# mainboard_interface_v1_1.net
KiCad netlist of a schematic drawn in Altium Designer
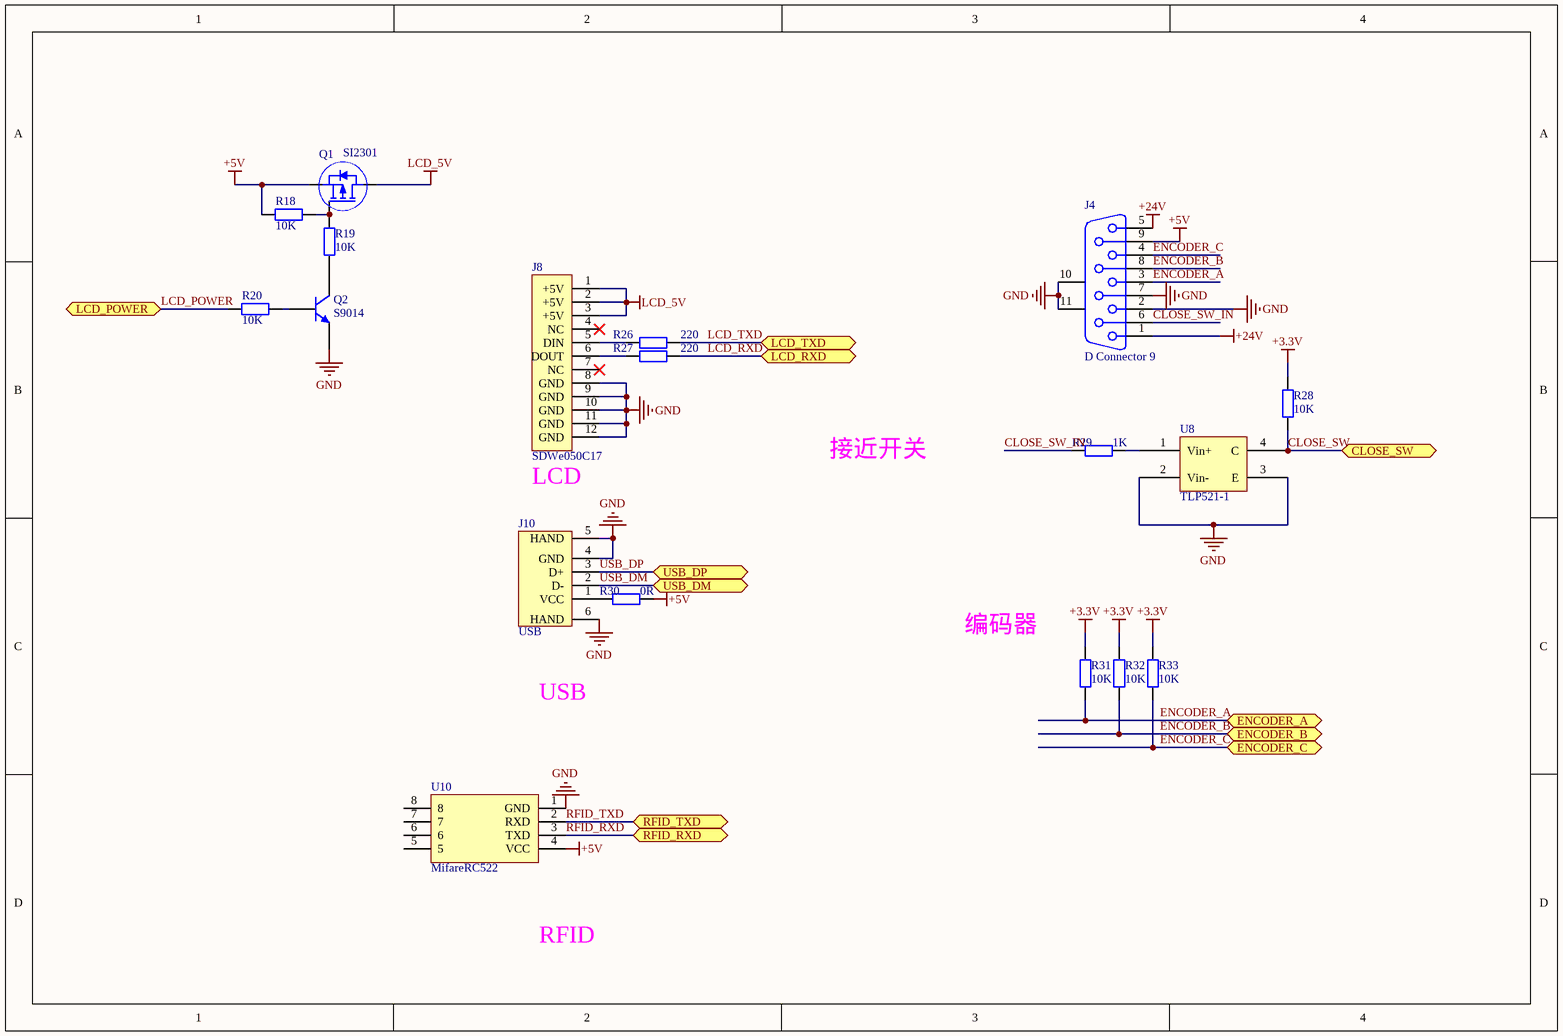
[diagram p0: mainboard_interface.v1.1.SchDoc]

(export (version "E")
  (design (tool "Eeschema 10.0.6"))
  (components
    (comp (ref "J4")
      (value "D Connector 9")
      (footprint "DSUB1.385-2H9")
      (description "Receptacle Assembly, 9 Position, Right Angle")
      (fields (field (name "PUBLISHER") "Altium Limited"))
      (libsource (lib "Miscellaneous Connectors") (part "D Connector 9"))
    )
    (comp (ref "J8")
      (value "SDWe050C17")
      (footprint "FCC1.0-10")
      (libsource (lib "Connector") (part "SH-12"))
    )
    (comp (ref "J10") (value "USB") (footprint "USB_FEMALE_A") (libsource (lib "Connector") (part "USB")))
    (comp (ref "Q1") (value "SI2301") (footprint "MOS-N_SOT-23") (libsource (lib "*") (part "MOS-P_SOT-23")))
    (comp (ref "Q2") (value "S9014") (footprint "901X_SOT-23") (libsource (lib "Componet") (part "NPN")))
    (comp (ref "R18")
      (value "10K")
      (footprint "0805")
      (description "Resistor")
      (fields (field (name "PUBLISHER") "Altium Limited"))
      (libsource (lib "") (part "Res2_1"))
    )
    (comp (ref "R19")
      (value "10K")
      (footprint "0805")
      (description "Resistor")
      (fields (field (name "PUBLISHER") "Altium Limited"))
      (libsource (lib "") (part "Res2_2"))
    )
    (comp (ref "R20")
      (value "10K")
      (footprint "0805")
      (description "Resistor")
      (fields (field (name "PUBLISHER") "Altium Limited"))
      (libsource (lib "") (part "Res2_1"))
    )
    (comp (ref "R26")
      (value "220")
      (footprint "0805")
      (description "Resistor")
      (fields (field (name "PUBLISHER") "Altium Limited"))
      (libsource (lib "") (part "Res2_1"))
    )
    (comp (ref "R27")
      (value "220")
      (footprint "0805")
      (description "Resistor")
      (fields (field (name "PUBLISHER") "Altium Limited"))
      (libsource (lib "") (part "Res2_1"))
    )
    (comp (ref "R28")
      (value "10K")
      (footprint "0805")
      (description "Resistor")
      (fields (field (name "PUBLISHER") "Altium Limited"))
      (libsource (lib "TIAN's Schlib") (part "Res2"))
    )
    (comp (ref "R29")
      (value "1K")
      (footprint "0805")
      (description "Resistor")
      (fields (field (name "PUBLISHER") "Altium Limited"))
      (libsource (lib "") (part "Res2_3"))
    )
    (comp (ref "R30")
      (value "0R")
      (footprint "0805")
      (description "Resistor")
      (fields (field (name "PUBLISHER") "Altium Limited"))
      (libsource (lib "") (part "Res2_3"))
    )
    (comp (ref "R31")
      (value "10K")
      (footprint "0805")
      (description "Resistor")
      (fields (field (name "PUBLISHER") "Altium Limited"))
      (libsource (lib "TIAN's Schlib") (part "Res2"))
    )
    (comp (ref "R32")
      (value "10K")
      (footprint "0805")
      (description "Resistor")
      (fields (field (name "PUBLISHER") "Altium Limited"))
      (libsource (lib "TIAN's Schlib") (part "Res2"))
    )
    (comp (ref "R33")
      (value "10K")
      (footprint "0805")
      (description "Resistor")
      (fields (field (name "PUBLISHER") "Altium Limited"))
      (libsource (lib "TIAN's Schlib") (part "Res2"))
    )
    (comp (ref "U8") (value "TLP521-1") (footprint "DIP-4") (libsource (lib "Chip") (part "TLP521-1")))
    (comp (ref "U10")
      (value "MifareRC522")
      (footprint "MifareRC522")
      (libsource (lib "Componet") (part "MifareRC522"))
    )
  )
  (nets
    (net (code "1") (name "+3.3V") (class "Default")
      (node (ref "R28") (pin "1") (pinfunction "1_1") (pintype "passive"))
      (node (ref "R31") (pin "1") (pinfunction "1_1") (pintype "passive"))
      (node (ref "R32") (pin "1") (pinfunction "1_1") (pintype "passive"))
      (node (ref "R33") (pin "1") (pinfunction "1_1") (pintype "passive"))
    )
    (net (code "2") (name "+5V") (class "Default")
      (node (ref "J4") (pin "9") (pinfunction "9_9") (pintype "passive"))
      (node (ref "Q1") (pin "S") (pinfunction "S_S") (pintype "passive"))
      (node (ref "R18") (pin "1") (pinfunction "1_1") (pintype "passive"))
      (node (ref "R30") (pin "1") (pinfunction "1_1") (pintype "passive"))
      (node (ref "U10") (pin "4") (pinfunction "VCC_4") (pintype "passive"))
    )
    (net (code "3") (name "+24V") (class "Default")
      (node (ref "J4") (pin "1") (pinfunction "1_1") (pintype "passive"))
      (node (ref "J4") (pin "5") (pinfunction "5_5") (pintype "passive"))
    )
    (net (code "4") (name "/CLOSE_SW") (class "Default")
      (node (ref "R28") (pin "2") (pinfunction "2_2") (pintype "passive"))
      (node (ref "U8") (pin "4") (pinfunction "C_4") (pintype "passive"))
    )
    (net (code "5") (name "/CLOSE_SW_IN") (class "Default")
      (node (ref "J4") (pin "6") (pinfunction "6_6") (pintype "passive"))
      (node (ref "R29") (pin "2") (pinfunction "2_2") (pintype "passive"))
    )
    (net (code "6") (name "/ENCODER_A") (class "Default")
      (node (ref "J4") (pin "3") (pinfunction "3_3") (pintype "passive"))
      (node (ref "R31") (pin "2") (pinfunction "2_2") (pintype "passive"))
    )
    (net (code "7") (name "/ENCODER_B") (class "Default")
      (node (ref "J4") (pin "8") (pinfunction "8_8") (pintype "passive"))
      (node (ref "R32") (pin "2") (pinfunction "2_2") (pintype "passive"))
    )
    (net (code "8") (name "/ENCODER_C") (class "Default")
      (node (ref "J4") (pin "4") (pinfunction "4_4") (pintype "passive"))
      (node (ref "R33") (pin "2") (pinfunction "2_2") (pintype "passive"))
    )
    (net (code "9") (name "/LCD_POWER") (class "Default")
      (node (ref "R20") (pin "1") (pinfunction "1_1") (pintype "passive"))
    )
    (net (code "10") (name "/LCD_RXD") (class "Default")
      (node (ref "R27") (pin "2") (pinfunction "2_2") (pintype "passive"))
    )
    (net (code "11") (name "/LCD_TXD") (class "Default")
      (node (ref "R26") (pin "2") (pinfunction "2_2") (pintype "passive"))
    )
    (net (code "12") (name "/RFID_RXD") (class "Default")
      (node (ref "U10") (pin "3") (pinfunction "TXD_3") (pintype "passive"))
    )
    (net (code "13") (name "/RFID_TXD") (class "Default")
      (node (ref "U10") (pin "2") (pinfunction "RXD_2") (pintype "passive"))
    )
    (net (code "14") (name "/USB_DM") (class "Default")
      (node (ref "J10") (pin "2") (pinfunction "D-_2") (pintype "passive"))
    )
    (net (code "15") (name "/USB_DP") (class "Default")
      (node (ref "J10") (pin "3") (pinfunction "D+_3") (pintype "passive"))
    )
    (net (code "16") (name "GND") (class "Default")
      (node (ref "J10") (pin "4") (pinfunction "GND_4") (pintype "passive"))
      (node (ref "J10") (pin "5") (pinfunction "HAND_5") (pintype "passive"))
      (node (ref "J10") (pin "6") (pinfunction "HAND_6") (pintype "passive"))
      (node (ref "J4") (pin "10") (pinfunction "MH1_10") (pintype "passive"))
      (node (ref "J4") (pin "11") (pinfunction "MH2_11") (pintype "passive"))
      (node (ref "J4") (pin "2") (pinfunction "2_2") (pintype "passive"))
      (node (ref "J4") (pin "7") (pinfunction "7_7") (pintype "passive"))
      (node (ref "J8") (pin "10") (pinfunction "GND_10") (pintype "passive"))
      (node (ref "J8") (pin "11") (pinfunction "GND_11") (pintype "passive"))
      (node (ref "J8") (pin "12") (pinfunction "GND_12") (pintype "passive"))
      (node (ref "J8") (pin "8") (pinfunction "GND_8") (pintype "passive"))
      (node (ref "J8") (pin "9") (pinfunction "GND_9") (pintype "passive"))
      (node (ref "Q2") (pin "3") (pinfunction "E_3") (pintype "passive"))
      (node (ref "U10") (pin "1") (pinfunction "GND_1") (pintype "passive"))
      (node (ref "U8") (pin "2") (pinfunction "Vin-_2") (pintype "passive"))
      (node (ref "U8") (pin "3") (pinfunction "E_3") (pintype "passive"))
    )
    (net (code "17") (name "LCD_5V") (class "Default")
      (node (ref "J8") (pin "1") (pinfunction "+5V_1") (pintype "passive"))
      (node (ref "J8") (pin "2") (pinfunction "+5V_2") (pintype "passive"))
      (node (ref "J8") (pin "3") (pinfunction "+5V_3") (pintype "passive"))
      (node (ref "Q1") (pin "D") (pinfunction "D_D") (pintype "passive"))
    )
    (net (code "18") (name "Net-(J8-DIN)") (class "Default")
      (node (ref "J8") (pin "5") (pinfunction "DIN_5") (pintype "passive"))
      (node (ref "R26") (pin "1") (pinfunction "1_1") (pintype "passive"))
    )
    (net (code "19") (name "Net-(J8-DOUT)") (class "Default")
      (node (ref "J8") (pin "6") (pinfunction "DOUT_6") (pintype "passive"))
      (node (ref "R27") (pin "1") (pinfunction "1_1") (pintype "passive"))
    )
    (net (code "20") (name "Net-(J10-VCC)") (class "Default")
      (node (ref "J10") (pin "1") (pinfunction "VCC_1") (pintype "passive"))
      (node (ref "R30") (pin "2") (pinfunction "2_2") (pintype "passive"))
    )
    (net (code "21") (name "Net-(Q1-PadG)") (class "Default")
      (node (ref "Q1") (pin "G") (pinfunction "G_G") (pintype "passive"))
      (node (ref "R18") (pin "2") (pinfunction "2_2") (pintype "passive"))
      (node (ref "R19") (pin "2") (pinfunction "2_2") (pintype "passive"))
    )
    (net (code "22") (name "Net-(Q2-B)") (class "Default")
      (node (ref "Q2") (pin "2") (pinfunction "B_2") (pintype "passive"))
      (node (ref "R20") (pin "2") (pinfunction "2_2") (pintype "passive"))
    )
    (net (code "23") (name "Net-(Q2-C)") (class "Default")
      (node (ref "Q2") (pin "1") (pinfunction "C_1") (pintype "passive"))
      (node (ref "R19") (pin "1") (pinfunction "1_1") (pintype "passive"))
    )
    (net (code "24") (name "Net-(U8-Vin+)") (class "Default")
      (node (ref "R29") (pin "1") (pinfunction "1_1") (pintype "passive"))
      (node (ref "U8") (pin "1") (pinfunction "Vin+_1") (pintype "passive"))
    )
    (net (code "25") (name "unconnected-(J8-NC-Pad4)") (class "Default")
      (node (ref "J8") (pin "4") (pinfunction "NC_4") (pintype "passive+no_connect"))
    )
    (net (code "26") (name "unconnected-(J8-NC-Pad7)") (class "Default")
      (node (ref "J8") (pin "7") (pinfunction "NC_7") (pintype "passive+no_connect"))
    )
    (net (code "27") (name "unconnected-(U10-Pad5)") (class "Default")
      (node (ref "U10") (pin "5") (pinfunction "5_5") (pintype "passive"))
    )
    (net (code "28") (name "unconnected-(U10-Pad6)") (class "Default")
      (node (ref "U10") (pin "6") (pinfunction "6_6") (pintype "passive"))
    )
    (net (code "29") (name "unconnected-(U10-Pad7)") (class "Default")
      (node (ref "U10") (pin "7") (pinfunction "7_7") (pintype "passive"))
    )
    (net (code "30") (name "unconnected-(U10-Pad8)") (class "Default")
      (node (ref "U10") (pin "8") (pinfunction "8_8") (pintype "passive"))
    )
  )
)
